# Precharge.net
KiCad netlist of a schematic drawn in Altium Designer
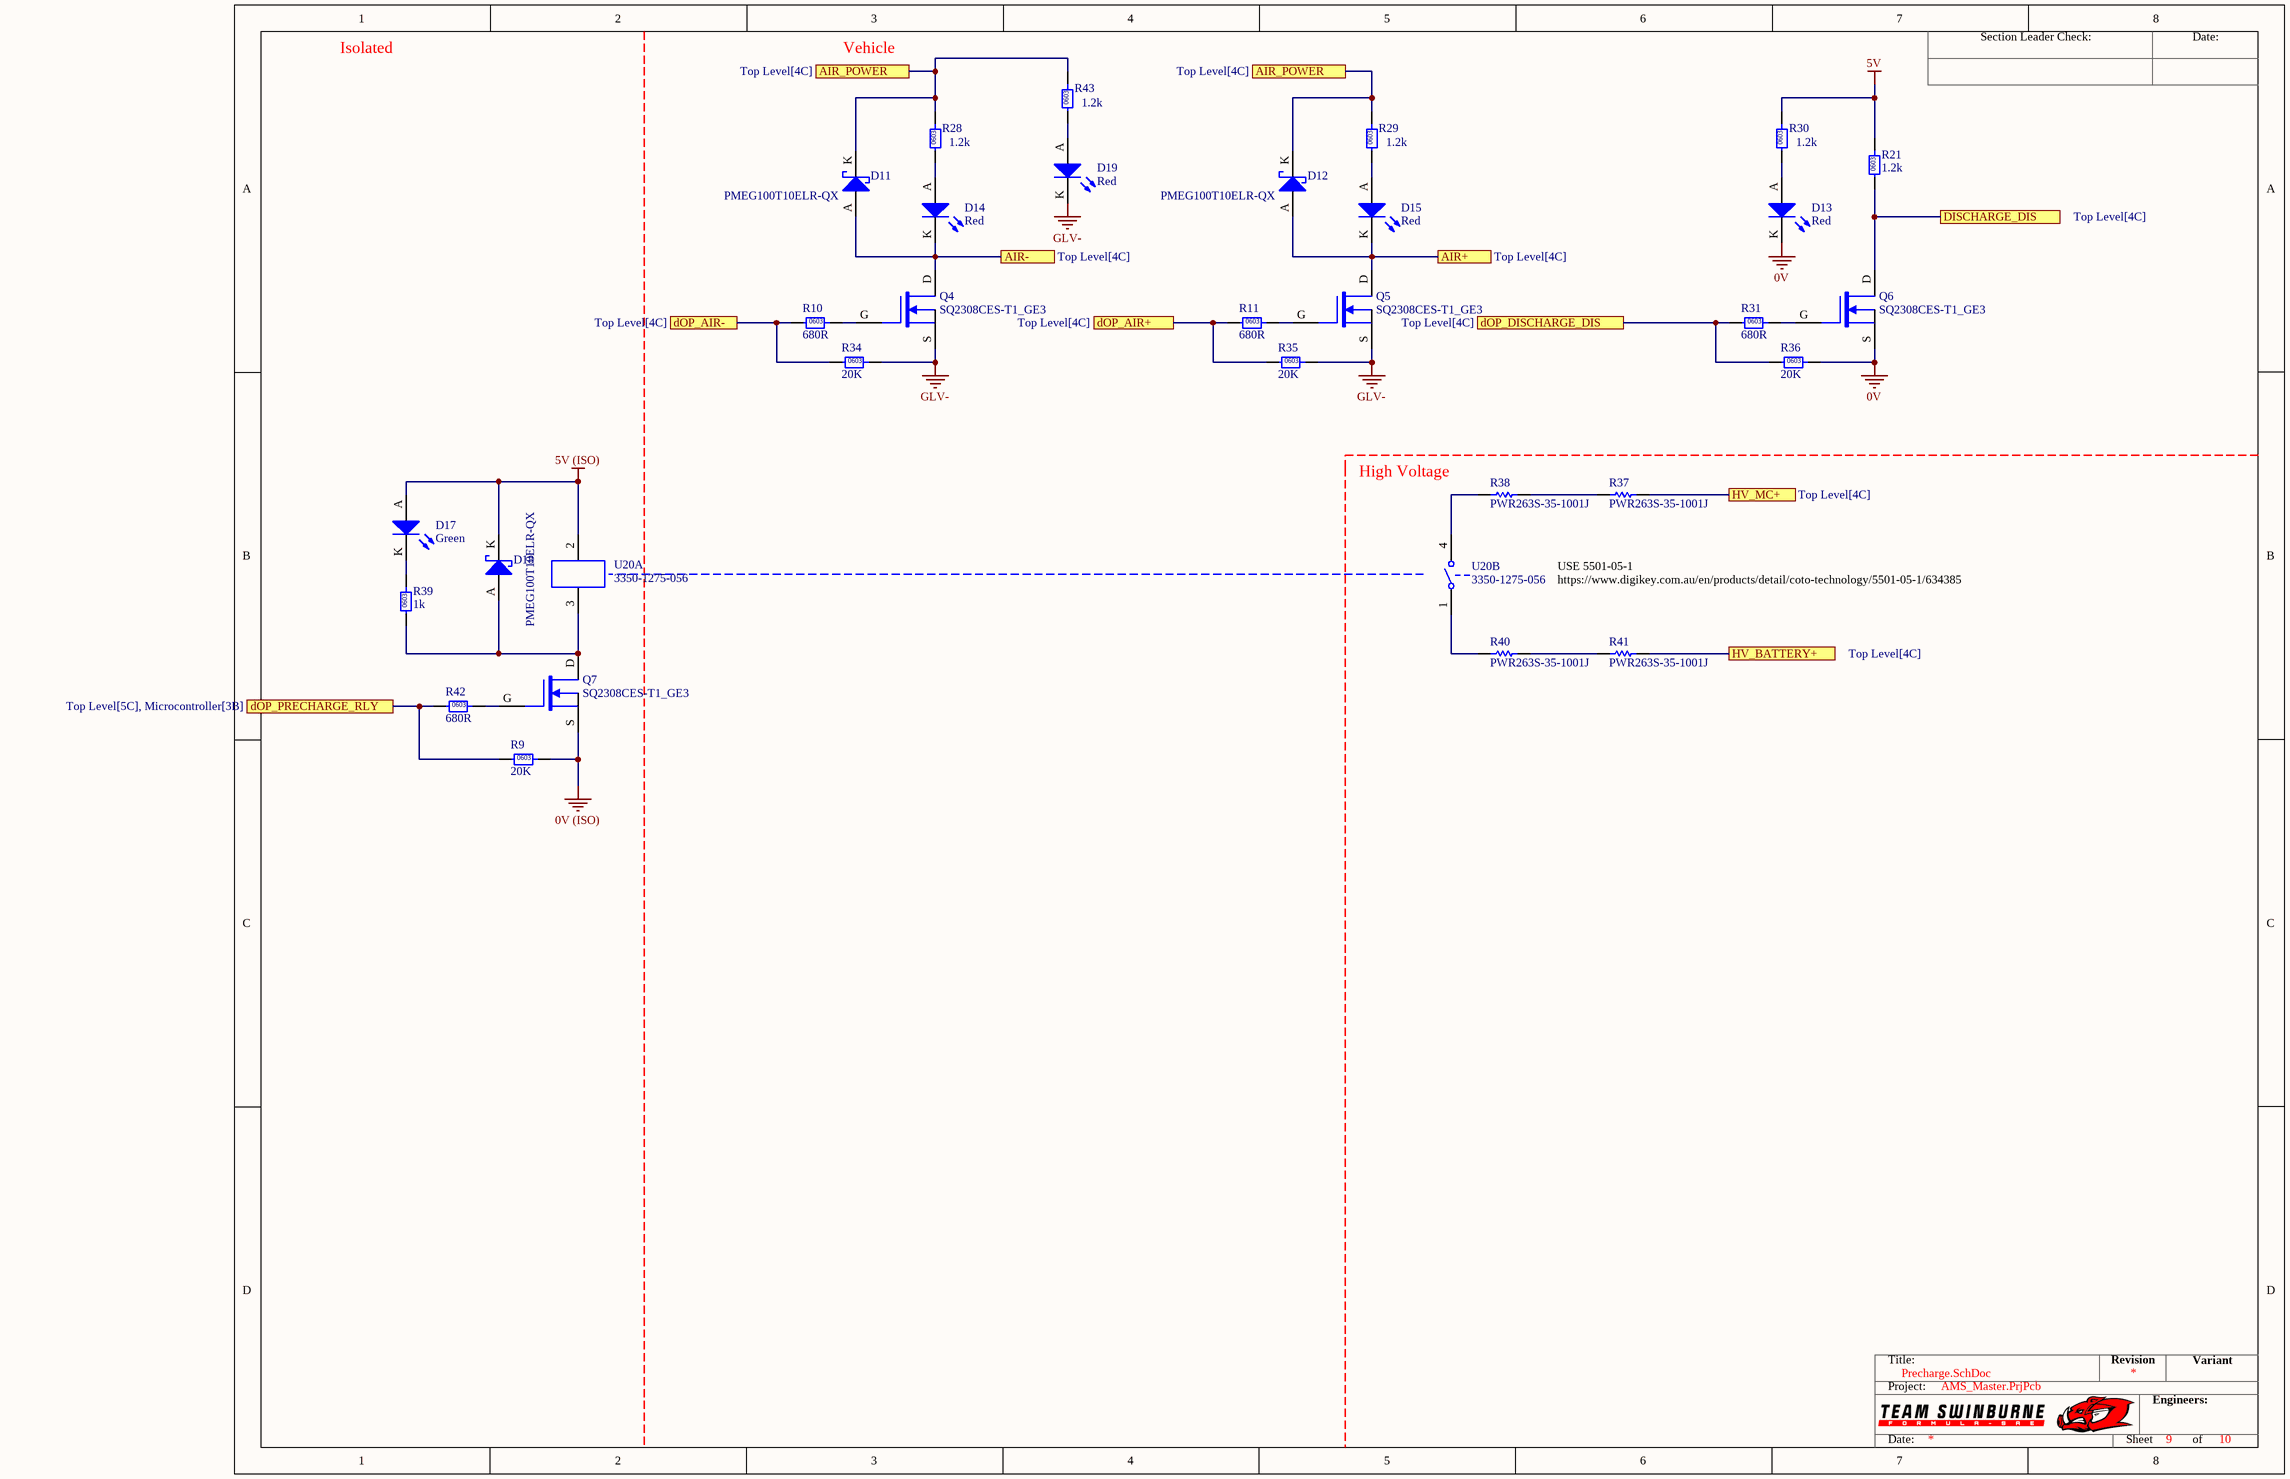
[diagram p0: Precharge.SchDoc]

(export (version "E")
  (design (tool "Eeschema 10.0.6"))
  (components
    (comp (ref "D11")
      (value "PMEG100T10ELR-QX")
      (footprint "NXP SOD123W")
      (fields
        (field (name "MANUFACTURER") "Nexperia USA Inc.")
        (field (name "DIGIKEY PART NUMBER") "1727-PMEG100T10ELR-QXCT-ND")
      )
      (libsource (lib "ts_standard_library") (part "Diode (Schottky)"))
    )
    (comp (ref "D12")
      (value "PMEG100T10ELR-QX")
      (footprint "NXP SOD123W")
      (fields
        (field (name "MANUFACTURER") "Nexperia USA Inc.")
        (field (name "DIGIKEY PART NUMBER") "1727-PMEG100T10ELR-QXCT-ND")
      )
      (libsource (lib "ts_standard_library") (part "Diode (Schottky)"))
    )
    (comp (ref "D13")
      (value "Red")
      (footprint "0805 LED")
      (description "Red LED Indication - Discrete 1.75V 0805 (2012 Metric)")
      (fields (field (name "PART NUMBER") "SML-210LTT86") (field (name "MANUFACTURER") "ROHM Semiconductor"))
      (libsource (lib "ts_standard_library") (part "LED"))
    )
    (comp (ref "D14")
      (value "Red")
      (footprint "0805 LED")
      (description "Red LED Indication - Discrete 1.75V 0805 (2012 Metric)")
      (fields (field (name "PART NUMBER") "SML-210LTT86") (field (name "MANUFACTURER") "ROHM Semiconductor"))
      (libsource (lib "ts_standard_library") (part "LED"))
    )
    (comp (ref "D15")
      (value "Red")
      (footprint "0805 LED")
      (description "Red LED Indication - Discrete 1.75V 0805 (2012 Metric)")
      (fields (field (name "PART NUMBER") "SML-210LTT86") (field (name "MANUFACTURER") "ROHM Semiconductor"))
      (libsource (lib "ts_standard_library") (part "LED"))
    )
    (comp (ref "D17")
      (value "Green")
      (footprint "0805 LED")
      (description "Green LED Indication - Discrete 1.75V 0805 (2012 Metric)")
      (fields (field (name "PART NUMBER") "SML-210FTT86") (field (name "MANUFACTURER") "ROHM Semiconductor"))
      (libsource (lib "ts_20-standard-library") (part "LED"))
    )
    (comp (ref "D18")
      (value "PMEG100T10ELR-QX")
      (footprint "NXP SOD123W")
      (fields
        (field (name "MANUFACTURER") "Nexperia USA Inc.")
        (field (name "DIGIKEY PART NUMBER") "1727-PMEG100T10ELR-QXCT-ND")
      )
      (libsource (lib "ts_standard_library") (part "Diode (Schottky)"))
    )
    (comp (ref "D19")
      (value "Red")
      (footprint "0805 LED")
      (description "Red LED Indication - Discrete 1.75V 0805 (2012 Metric)")
      (fields (field (name "PART NUMBER") "SML-210LTT86") (field (name "MANUFACTURER") "ROHM Semiconductor"))
      (libsource (lib "ts_standard_library") (part "LED"))
    )
    (comp (ref "Q4")
      (value "SQ2308CES-T1_GE3")
      (footprint "VSHY SOT-23-3")
      (description "MOSFET N-CH 60V 2.3A SOT23")
      (fields
        (field (name "MANUFACTURER") "Vishay Siliconix")
        (field (name "DIGIKEY PART NUMBER") "SQ2308CES-T1_GE3CT-ND")
        (field (name "PUBLISHER") "Altium Limited")
      )
      (libsource (lib "ts_standard_library") (part "MOSFET-N"))
    )
    (comp (ref "Q5")
      (value "SQ2308CES-T1_GE3")
      (footprint "VSHY SOT-23-3")
      (description "MOSFET N-CH 60V 2.3A SOT23")
      (fields
        (field (name "MANUFACTURER") "Vishay Siliconix")
        (field (name "DIGIKEY PART NUMBER") "SQ2308CES-T1_GE3CT-ND")
        (field (name "PUBLISHER") "Altium Limited")
      )
      (libsource (lib "ts_standard_library") (part "MOSFET-N"))
    )
    (comp (ref "Q6")
      (value "SQ2308CES-T1_GE3")
      (footprint "VSHY SOT-23-3")
      (description "MOSFET N-CH 60V 2.3A SOT23")
      (fields
        (field (name "MANUFACTURER") "Vishay Siliconix")
        (field (name "DIGIKEY PART NUMBER") "SQ2308CES-T1_GE3CT-ND")
        (field (name "PUBLISHER") "Altium Limited")
      )
      (libsource (lib "ts_standard_library") (part "MOSFET-N"))
    )
    (comp (ref "Q7")
      (value "SQ2308CES-T1_GE3")
      (footprint "VSHY SOT-23-3")
      (description "MOSFET N-CH 60V 2.3A SOT23")
      (fields
        (field (name "MANUFACTURER") "Vishay Siliconix")
        (field (name "DIGIKEY PART NUMBER") "SQ2308CES-T1_GE3CT-ND")
        (field (name "PUBLISHER") "Altium Limited")
      )
      (libsource (lib "ts_standard_library") (part "MOSFET-N"))
    )
    (comp (ref "R9")
      (value "20K")
      (footprint "0603")
      (fields
        (field (name "PART NUMBER") "RC0603FR-0720KL")
        (field (name "MANUFACTURER") "YAGEO")
        (field (name "TOLERANCE") "0.01")
      )
      (libsource (lib "ts_standard_library") (part "Resistor 0603"))
    )
    (comp (ref "R10")
      (value "680R")
      (footprint "0603")
      (fields
        (field (name "PART NUMBER") "RC0603JR-13680RL")
        (field (name "MANUFACTURER") "YAGEO")
        (field (name "TOLERANCE") "0.01")
      )
      (libsource (lib "ts_standard_library") (part "Resistor 0603"))
    )
    (comp (ref "R11")
      (value "680R")
      (footprint "0603")
      (fields
        (field (name "PART NUMBER") "RC0603JR-13680RL")
        (field (name "MANUFACTURER") "YAGEO")
        (field (name "TOLERANCE") "0.01")
      )
      (libsource (lib "ts_standard_library") (part "Resistor 0603"))
    )
    (comp (ref "R21")
      (value "1.2k")
      (footprint "0603")
      (fields
        (field (name "PART NUMBER") "RC0603JR-071K2L")
        (field (name "MANUFACTURER") "YAGEO")
        (field (name "TOLERANCE") "0.01")
      )
      (libsource (lib "ts_standard_library") (part "Resistor 0603"))
    )
    (comp (ref "R28")
      (value "1.2k")
      (footprint "0603")
      (fields
        (field (name "PART NUMBER") "RC0603JR-071K2L")
        (field (name "MANUFACTURER") "YAGEO")
        (field (name "TOLERANCE") "0.01")
      )
      (libsource (lib "ts_standard_library") (part "Resistor 0603"))
    )
    (comp (ref "R29")
      (value "1.2k")
      (footprint "0603")
      (fields
        (field (name "PART NUMBER") "RC0603JR-071K2L")
        (field (name "MANUFACTURER") "YAGEO")
        (field (name "TOLERANCE") "0.01")
      )
      (libsource (lib "ts_standard_library") (part "Resistor 0603"))
    )
    (comp (ref "R30")
      (value "1.2k")
      (footprint "0603")
      (fields
        (field (name "PART NUMBER") "RC0603JR-071K2L")
        (field (name "MANUFACTURER") "YAGEO")
        (field (name "TOLERANCE") "0.01")
      )
      (libsource (lib "ts_standard_library") (part "Resistor 0603"))
    )
    (comp (ref "R31")
      (value "680R")
      (footprint "0603")
      (fields
        (field (name "PART NUMBER") "RC0603JR-13680RL")
        (field (name "MANUFACTURER") "YAGEO")
        (field (name "TOLERANCE") "0.01")
      )
      (libsource (lib "ts_standard_library") (part "Resistor 0603"))
    )
    (comp (ref "R34")
      (value "20K")
      (footprint "0603")
      (fields
        (field (name "PART NUMBER") "RC0603FR-0720KL")
        (field (name "MANUFACTURER") "YAGEO")
        (field (name "TOLERANCE") "0.01")
      )
      (libsource (lib "ts_standard_library") (part "Resistor 0603"))
    )
    (comp (ref "R35")
      (value "20K")
      (footprint "0603")
      (fields
        (field (name "PART NUMBER") "RC0603FR-0720KL")
        (field (name "MANUFACTURER") "YAGEO")
        (field (name "TOLERANCE") "0.01")
      )
      (libsource (lib "ts_standard_library") (part "Resistor 0603"))
    )
    (comp (ref "R36")
      (value "20K")
      (footprint "0603")
      (fields
        (field (name "PART NUMBER") "RC0603FR-0720KL")
        (field (name "MANUFACTURER") "YAGEO")
        (field (name "TOLERANCE") "0.01")
      )
      (libsource (lib "ts_standard_library") (part "Resistor 0603"))
    )
    (comp (ref "R37")
      (value "PWR263S-35-1001J")
      (footprint "B TO-263")
      (fields
        (field (name "MANUFACTURER") "Bournes Inc")
        (field (name "TOLERANCE") "0.05")
        (field (name "DIGIKEY PART NUMBER") "PWR263S-35-1001J-ND")
      )
      (libsource (lib "Team Swinburne") (part "Resistor"))
    )
    (comp (ref "R38")
      (value "PWR263S-35-1001J")
      (footprint "B TO-263")
      (fields
        (field (name "MANUFACTURER") "Bournes Inc")
        (field (name "TOLERANCE") "0.05")
        (field (name "DIGIKEY PART NUMBER") "PWR263S-35-1001J-ND")
      )
      (libsource (lib "Team Swinburne") (part "Resistor"))
    )
    (comp (ref "R39")
      (value "1k")
      (footprint "0603")
      (fields
        (field (name "PART NUMBER") "RC0603FR-071KL")
        (field (name "MANUFACTURER") "YAGEO")
        (field (name "TOLERANCE") "0.01")
      )
      (libsource (lib "ts_standard_library") (part "Resistor 0603"))
    )
    (comp (ref "R40")
      (value "PWR263S-35-1001J")
      (footprint "B TO-263")
      (fields
        (field (name "MANUFACTURER") "Bournes Inc")
        (field (name "TOLERANCE") "0.05")
        (field (name "DIGIKEY PART NUMBER") "PWR263S-35-1001J-ND")
      )
      (libsource (lib "Team Swinburne") (part "Resistor"))
    )
    (comp (ref "R41")
      (value "PWR263S-35-1001J")
      (footprint "B TO-263")
      (fields
        (field (name "MANUFACTURER") "Bournes Inc")
        (field (name "TOLERANCE") "0.05")
        (field (name "DIGIKEY PART NUMBER") "PWR263S-35-1001J-ND")
      )
      (libsource (lib "Team Swinburne") (part "Resistor"))
    )
    (comp (ref "R42")
      (value "680R")
      (footprint "0603")
      (fields
        (field (name "PART NUMBER") "RC0603JR-13680RL")
        (field (name "MANUFACTURER") "YAGEO")
        (field (name "TOLERANCE") "0.01")
      )
      (libsource (lib "ts_standard_library") (part "Resistor 0603"))
    )
    (comp (ref "R43")
      (value "1.2k")
      (footprint "0603")
      (fields
        (field (name "PART NUMBER") "RC0603JR-071K2L")
        (field (name "MANUFACTURER") "YAGEO")
        (field (name "TOLERANCE") "0.01")
      )
      (libsource (lib "ts_standard_library") (part "Resistor 0603"))
    )
    (comp (ref "U20")
      (value "3350-1275-056")
      (footprint "CI SPST")
      (description "RELAY REED HV SPST 200W 3A 5V (NO)")
      (fields
        (field (name "MANUFACTURER") "Comus International")
        (field (name "DIGIKEY PART NUMBER") "1835-1036-ND")
      )
      (libsource (lib "") (part "3350-1275-056_1"))
    )
  )
  (nets
    (net (code "1") (name "/AIR+") (class "Default")
      (node (ref "D12") (pin "A") (pinfunction "A_A") (pintype "passive"))
      (node (ref "D15") (pin "K") (pinfunction "K_K") (pintype "passive"))
      (node (ref "Q5") (pin "D") (pinfunction "D_D") (pintype "passive"))
    )
    (net (code "2") (name "/AIR-") (class "Default")
      (node (ref "D11") (pin "A") (pinfunction "A_A") (pintype "passive"))
      (node (ref "D14") (pin "K") (pinfunction "K_K") (pintype "passive"))
      (node (ref "Q4") (pin "D") (pinfunction "D_D") (pintype "passive"))
    )
    (net (code "3") (name "/AIR_POWER") (class "Default")
      (node (ref "D11") (pin "K") (pinfunction "K_K") (pintype "passive"))
      (node (ref "D12") (pin "K") (pinfunction "K_K") (pintype "passive"))
      (node (ref "R28") (pin "2") (pinfunction "2_2") (pintype "passive"))
      (node (ref "R29") (pin "2") (pinfunction "2_2") (pintype "passive"))
      (node (ref "R43") (pin "2") (pinfunction "2_2") (pintype "passive"))
    )
    (net (code "4") (name "/DISCHARGE_DIS") (class "Default")
      (node (ref "Q6") (pin "D") (pinfunction "D_D") (pintype "passive"))
      (node (ref "R21") (pin "1") (pinfunction "1_1") (pintype "passive"))
    )
    (net (code "5") (name "/HV_BATTERY+") (class "Default")
      (node (ref "R41") (pin "2") (pinfunction "2_2") (pintype "passive"))
    )
    (net (code "6") (name "/HV_MC+") (class "Default")
      (node (ref "R37") (pin "1") (pinfunction "1_1") (pintype "passive"))
    )
    (net (code "7") (name "/dOP_AIR+") (class "Default")
      (node (ref "R11") (pin "1") (pinfunction "1_1") (pintype "passive"))
      (node (ref "R35") (pin "1") (pinfunction "1_1") (pintype "passive"))
    )
    (net (code "8") (name "/dOP_AIR-") (class "Default")
      (node (ref "R10") (pin "1") (pinfunction "1_1") (pintype "passive"))
      (node (ref "R34") (pin "1") (pinfunction "1_1") (pintype "passive"))
    )
    (net (code "9") (name "/dOP_DISCHARGE_DIS") (class "Default")
      (node (ref "R31") (pin "1") (pinfunction "1_1") (pintype "passive"))
      (node (ref "R36") (pin "1") (pinfunction "1_1") (pintype "passive"))
    )
    (net (code "10") (name "/dOP_PRECHARGE_RLY") (class "Default")
      (node (ref "R42") (pin "1") (pinfunction "1_1") (pintype "passive"))
      (node (ref "R9") (pin "1") (pinfunction "1_1") (pintype "passive"))
    )
    (net (code "11") (name "0V") (class "Default")
      (node (ref "D13") (pin "K") (pinfunction "K_K") (pintype "passive"))
      (node (ref "Q6") (pin "S") (pinfunction "S_S") (pintype "passive"))
      (node (ref "R36") (pin "2") (pinfunction "2_2") (pintype "passive"))
    )
    (net (code "12") (name "0V (ISO)") (class "Default")
      (node (ref "Q7") (pin "S") (pinfunction "S_S") (pintype "passive"))
      (node (ref "R9") (pin "2") (pinfunction "2_2") (pintype "passive"))
    )
    (net (code "13") (name "5V") (class "Default")
      (node (ref "R21") (pin "2") (pinfunction "2_2") (pintype "passive"))
      (node (ref "R30") (pin "2") (pinfunction "2_2") (pintype "passive"))
    )
    (net (code "14") (name "5V (ISO)") (class "Default")
      (node (ref "D17") (pin "A") (pinfunction "A_A") (pintype "passive"))
      (node (ref "D18") (pin "K") (pinfunction "K_K") (pintype "passive"))
      (node (ref "U20") (pin "2") (pinfunction "2_2") (pintype "passive"))
    )
    (net (code "15") (name "GLV-") (class "Default")
      (node (ref "D19") (pin "K") (pinfunction "K_K") (pintype "passive"))
      (node (ref "Q4") (pin "S") (pinfunction "S_S") (pintype "passive"))
      (node (ref "Q5") (pin "S") (pinfunction "S_S") (pintype "passive"))
      (node (ref "R34") (pin "2") (pinfunction "2_2") (pintype "passive"))
      (node (ref "R35") (pin "2") (pinfunction "2_2") (pintype "passive"))
    )
    (net (code "16") (name "Net-(D13-PadA)") (class "Default")
      (node (ref "D13") (pin "A") (pinfunction "A_A") (pintype "passive"))
      (node (ref "R30") (pin "1") (pinfunction "1_1") (pintype "passive"))
    )
    (net (code "17") (name "Net-(D14-PadA)") (class "Default")
      (node (ref "D14") (pin "A") (pinfunction "A_A") (pintype "passive"))
      (node (ref "R28") (pin "1") (pinfunction "1_1") (pintype "passive"))
    )
    (net (code "18") (name "Net-(D15-PadA)") (class "Default")
      (node (ref "D15") (pin "A") (pinfunction "A_A") (pintype "passive"))
      (node (ref "R29") (pin "1") (pinfunction "1_1") (pintype "passive"))
    )
    (net (code "19") (name "Net-(D17-PadK)") (class "Default")
      (node (ref "D17") (pin "K") (pinfunction "K_K") (pintype "passive"))
      (node (ref "R39") (pin "2") (pinfunction "2_2") (pintype "passive"))
    )
    (net (code "20") (name "Net-(D18-PadA)") (class "Default")
      (node (ref "D18") (pin "A") (pinfunction "A_A") (pintype "passive"))
      (node (ref "Q7") (pin "D") (pinfunction "D_D") (pintype "passive"))
      (node (ref "R39") (pin "1") (pinfunction "1_1") (pintype "passive"))
      (node (ref "U20") (pin "3") (pinfunction "3_3") (pintype "passive"))
    )
    (net (code "21") (name "Net-(D19-PadA)") (class "Default")
      (node (ref "D19") (pin "A") (pinfunction "A_A") (pintype "passive"))
      (node (ref "R43") (pin "1") (pinfunction "1_1") (pintype "passive"))
    )
    (net (code "22") (name "Net-(Q4-PadG)") (class "Default")
      (node (ref "Q4") (pin "G") (pinfunction "G_G") (pintype "passive"))
      (node (ref "R10") (pin "2") (pinfunction "2_2") (pintype "passive"))
    )
    (net (code "23") (name "Net-(Q5-PadG)") (class "Default")
      (node (ref "Q5") (pin "G") (pinfunction "G_G") (pintype "passive"))
      (node (ref "R11") (pin "2") (pinfunction "2_2") (pintype "passive"))
    )
    (net (code "24") (name "Net-(Q6-PadG)") (class "Default")
      (node (ref "Q6") (pin "G") (pinfunction "G_G") (pintype "passive"))
      (node (ref "R31") (pin "2") (pinfunction "2_2") (pintype "passive"))
    )
    (net (code "25") (name "Net-(Q7-PadG)") (class "Default")
      (node (ref "Q7") (pin "G") (pinfunction "G_G") (pintype "passive"))
      (node (ref "R42") (pin "2") (pinfunction "2_2") (pintype "passive"))
    )
    (net (code "26") (name "Net-(R37-Pad2)") (class "Default")
      (node (ref "R37") (pin "2") (pinfunction "2_2") (pintype "passive"))
      (node (ref "R38") (pin "1") (pinfunction "1_1") (pintype "passive"))
    )
    (net (code "27") (name "Net-(R38-Pad2)") (class "Default")
      (node (ref "R38") (pin "2") (pinfunction "2_2") (pintype "passive"))
      (node (ref "U20") (pin "4") (pinfunction "4_4") (pintype "passive"))
    )
    (net (code "28") (name "Net-(R40-Pad1)") (class "Default")
      (node (ref "R40") (pin "1") (pinfunction "1_1") (pintype "passive"))
      (node (ref "U20") (pin "1") (pinfunction "1_1") (pintype "passive"))
    )
    (net (code "29") (name "Net-(R40-Pad2)") (class "Default")
      (node (ref "R40") (pin "2") (pinfunction "2_2") (pintype "passive"))
      (node (ref "R41") (pin "1") (pinfunction "1_1") (pintype "passive"))
    )
  )
)
